# 02_POWER_LED.net
KiCad netlist of a schematic drawn in Altium Designer
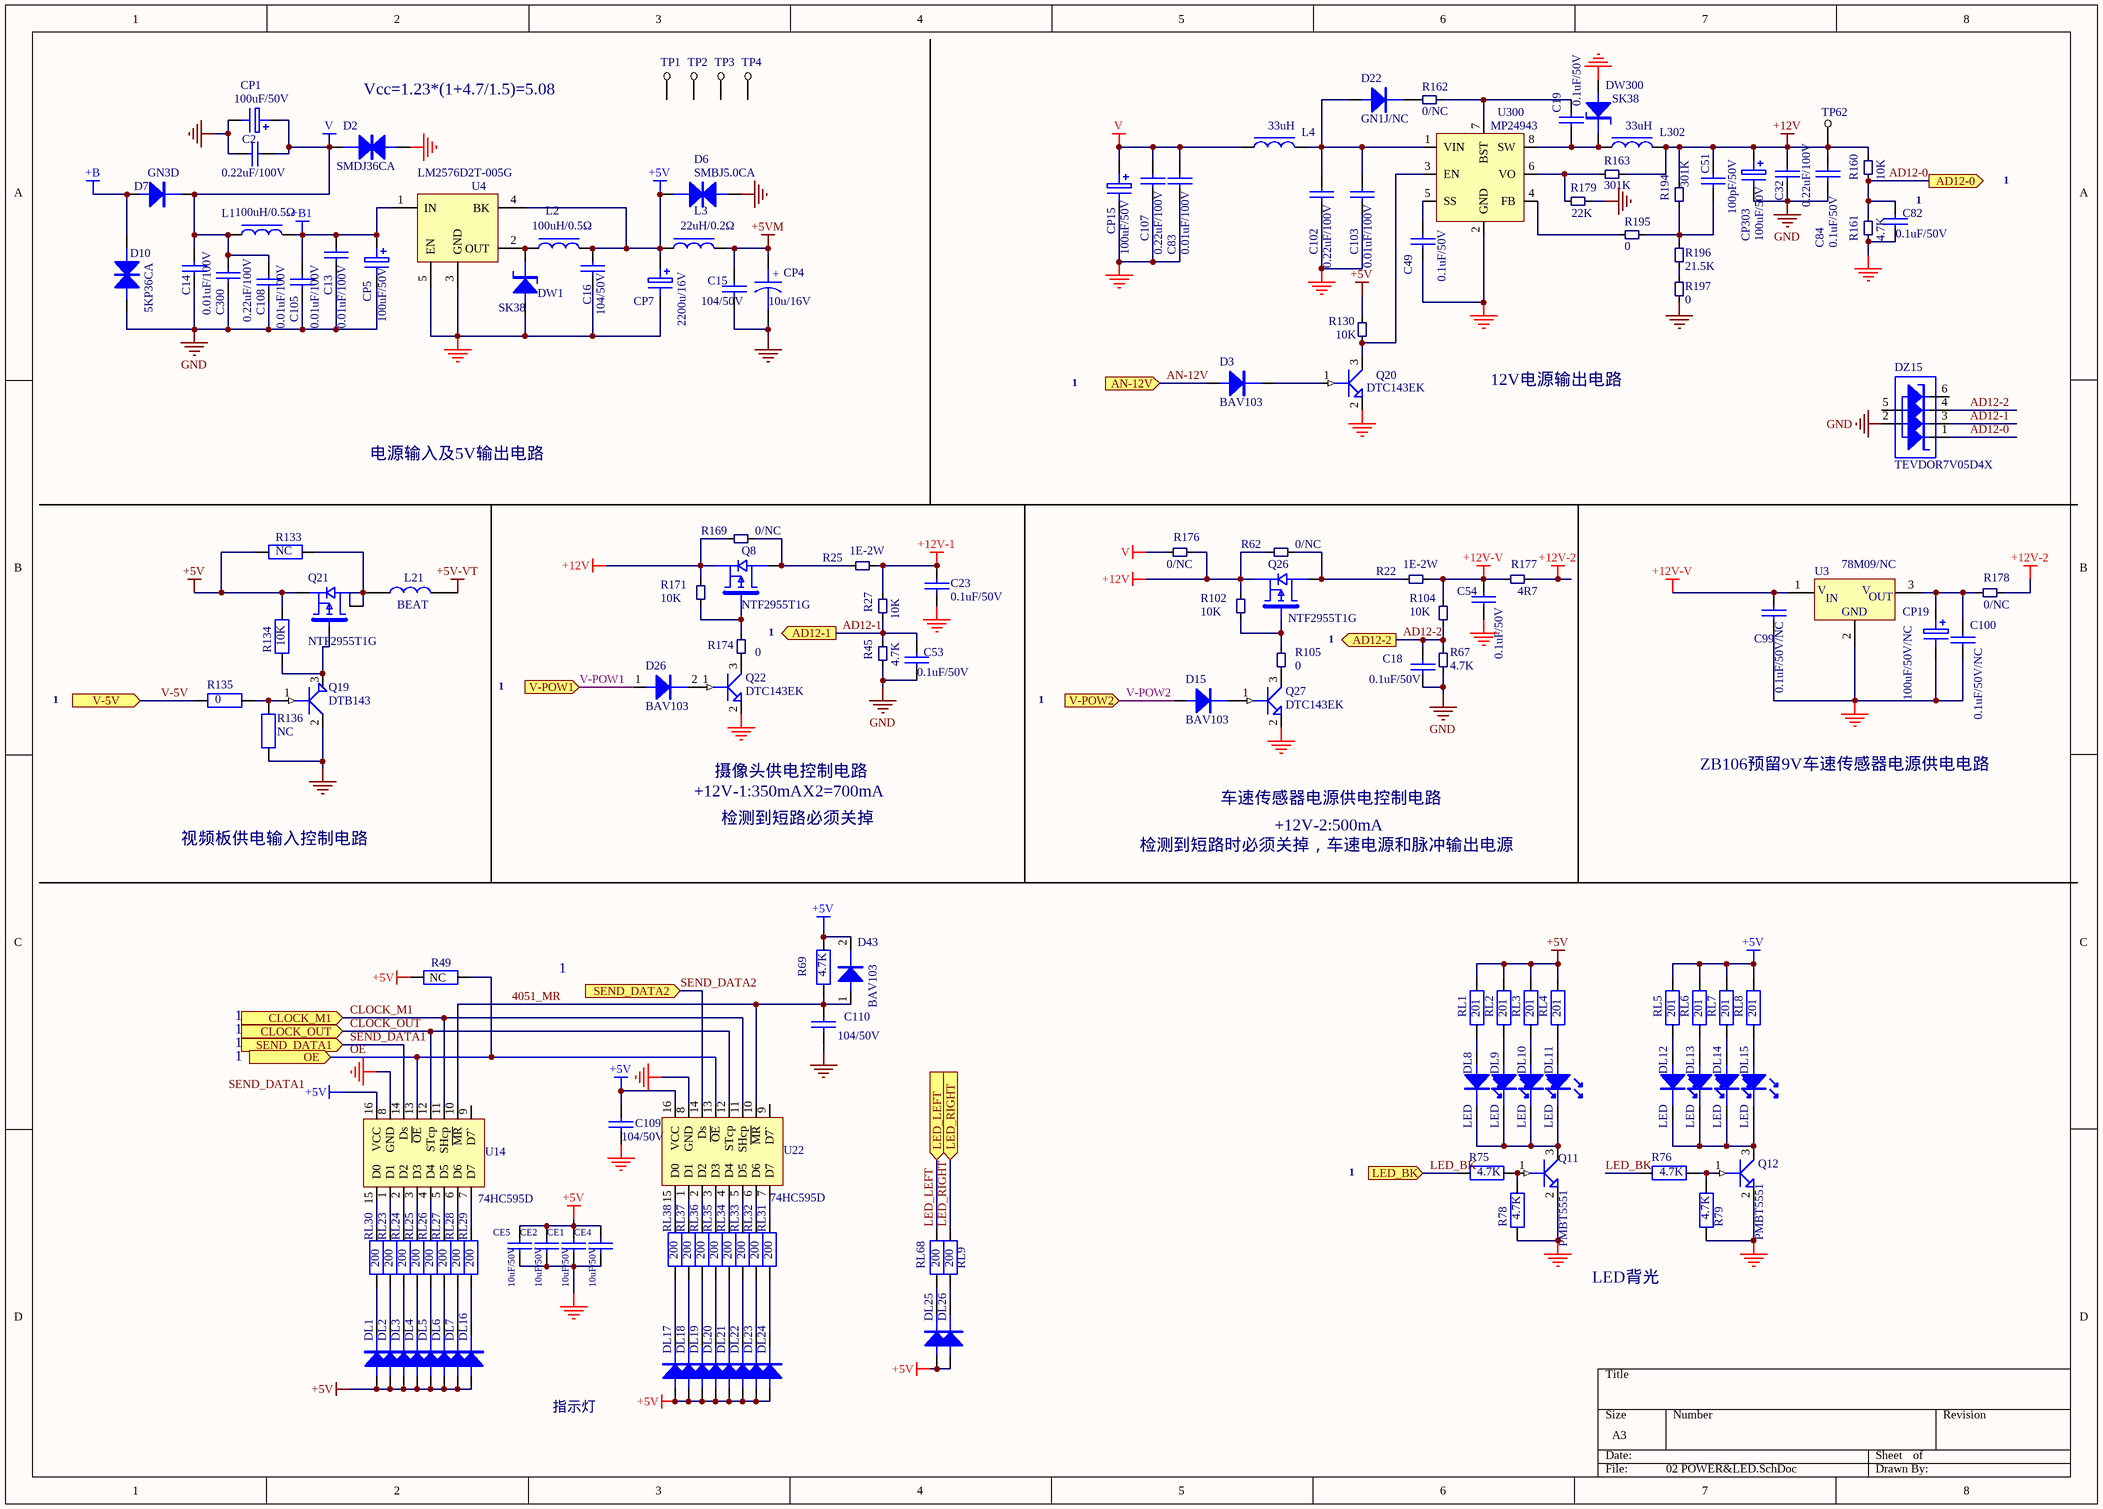
[diagram p0: 02 POWER&LED.SchDoc]

(export (version "E")
  (design (tool "Eeschema 10.0.6"))
  (components
    (comp (ref "C2")
      (value "0.22uF/100V")
      (footprint "CR1206")
      (description "Capacitor")
      (libsource (lib "*") (part "CAP"))
    )
    (comp (ref "C13")
      (value "0.01uF/100V")
      (footprint "CR0805")
      (description "Capacitor")
      (libsource (lib "*") (part "CAP"))
    )
    (comp (ref "C14")
      (value "0.01uF/100V")
      (footprint "CR0805")
      (description "Capacitor")
      (libsource (lib "*") (part "CAP"))
    )
    (comp (ref "C15")
      (value "104/50V")
      (footprint "CR0805")
      (description "Capacitor")
      (libsource (lib "*") (part "CAP"))
    )
    (comp (ref "C16")
      (value "104/50V")
      (footprint "CR0805")
      (description "Capacitor")
      (libsource (lib "*") (part "CAP"))
    )
    (comp (ref "C18")
      (value "0.1uF/50V")
      (footprint "CR0805")
      (description "Capacitor")
      (libsource (lib "*") (part "CAP"))
    )
    (comp (ref "C19")
      (value "0.1uF/50V")
      (footprint "CR0805")
      (description "Capacitor")
      (libsource (lib "*") (part "CAP"))
    )
    (comp (ref "C23")
      (value "0.1uF/50V")
      (footprint "CR0805")
      (description "Capacitor")
      (libsource (lib "*") (part "CAP"))
    )
    (comp (ref "C32")
      (value "0.22uF/100V")
      (footprint "CR1206")
      (description "Capacitor")
      (libsource (lib "*") (part "CAP"))
    )
    (comp (ref "C49")
      (value "0.1uF/50V")
      (footprint "CR0805")
      (description "Capacitor")
      (libsource (lib "*") (part "CAP"))
    )
    (comp (ref "C51")
      (value "100pF/50V")
      (footprint "CR0805")
      (description "Capacitor")
      (libsource (lib "*") (part "CAP"))
    )
    (comp (ref "C53")
      (value "0.1uF/50V")
      (footprint "CR0805")
      (description "Capacitor")
      (libsource (lib "*") (part "CAP"))
    )
    (comp (ref "C54")
      (value "0.1uF/50V")
      (footprint "CR0805")
      (description "Capacitor")
      (libsource (lib "*") (part "CAP"))
    )
    (comp (ref "C82")
      (value "0.1uF/50V")
      (footprint "CR0805")
      (description "Capacitor")
      (libsource (lib "*") (part "CAP"))
    )
    (comp (ref "C83")
      (value "0.01uF/100V")
      (footprint "CR0805")
      (description "Capacitor")
      (libsource (lib "*") (part "CAP"))
    )
    (comp (ref "C84")
      (value "0.1uF/50V")
      (footprint "CR0805")
      (description "Capacitor")
      (libsource (lib "*") (part "CAP"))
    )
    (comp (ref "C99")
      (value "0.1uF/50V/NC")
      (footprint "CR0805")
      (description "Capacitor")
      (libsource (lib "*") (part "CAP"))
    )
    (comp (ref "C100")
      (value "0.1uF/50V/NC")
      (footprint "CR0805")
      (description "Capacitor")
      (libsource (lib "*") (part "CAP"))
    )
    (comp (ref "C102")
      (value "0.22uF/100V")
      (footprint "CR1206")
      (description "Capacitor")
      (libsource (lib "*") (part "CAP"))
    )
    (comp (ref "C103")
      (value "0.01uF/100V")
      (footprint "CR0805")
      (description "Capacitor")
      (libsource (lib "*") (part "CAP"))
    )
    (comp (ref "C105")
      (value "0.01uF/100V")
      (footprint "CR0805")
      (description "Capacitor")
      (libsource (lib "*") (part "CAP"))
    )
    (comp (ref "C107")
      (value "0.22uF/100V")
      (footprint "CR1206")
      (description "Capacitor")
      (libsource (lib "*") (part "CAP"))
    )
    (comp (ref "C108")
      (value "0.01uF/100V")
      (footprint "CR0805")
      (description "Capacitor")
      (libsource (lib "*") (part "CAP"))
    )
    (comp (ref "C109")
      (value "104/50V")
      (footprint "CR0805")
      (description "Capacitor")
      (libsource (lib "*") (part "CAP"))
    )
    (comp (ref "C110")
      (value "104/50V")
      (footprint "CR0805")
      (description "Capacitor")
      (libsource (lib "*") (part "CAP"))
    )
    (comp (ref "C300")
      (value "0.22uF/100V")
      (footprint "CR1206")
      (description "Capacitor")
      (libsource (lib "*") (part "CAP"))
    )
    (comp (ref "CE1")
      (value "10uF/50V")
      (footprint "CR1206")
      (description "Capacitor")
      (libsource (lib "*") (part "CAP"))
    )
    (comp (ref "CE2")
      (value "10uF/50V")
      (footprint "CR1206")
      (description "Capacitor")
      (libsource (lib "*") (part "CAP"))
    )
    (comp (ref "CE4")
      (value "10uF/50V")
      (footprint "CR1206")
      (description "Capacitor")
      (libsource (lib "*") (part "CAP"))
    )
    (comp (ref "CE5")
      (value "10uF/50V")
      (footprint "CR1206")
      (description "Capacitor")
      (libsource (lib "*") (part "CAP"))
    )
    (comp (ref "CP1")
      (value "100uF/50V")
      (footprint "RB10")
      (description "电解电容")
      (libsource (lib "*") (part "ELECTRO1"))
    )
    (comp (ref "CP4")
      (value "10u/16V")
      (footprint "CE1206")
      (description "Capacitor")
      (libsource (lib "*") (part "CAPACITOR POL"))
    )
    (comp (ref "CP5")
      (value "100uF/50V")
      (footprint "RB5-1")
      (description "电解电容")
      (libsource (lib "*") (part "ELECTRO1"))
    )
    (comp (ref "CP7")
      (value "2200u/16V")
      (footprint "RB12.5")
      (description "电解电容")
      (libsource (lib "*") (part "ELECTRO1"))
    )
    (comp (ref "CP15")
      (value "100uF/50V")
      (footprint "RB5-1")
      (description "电解电容")
      (libsource (lib "*") (part "ELECTRO1"))
    )
    (comp (ref "CP19")
      (value "100uF/50V/NC")
      (footprint "RB5-1")
      (description "电解电容")
      (libsource (lib "*") (part "ELECTRO1"))
    )
    (comp (ref "CP303")
      (value "100uF/50V")
      (footprint "RB5-1")
      (description "电解电容")
      (libsource (lib "*") (part "ELECTRO1"))
    )
    (comp (ref "D2") (value "SMDJ36CA") (footprint "SMC-D") (libsource (lib "YDM-SQ-1SCH") (part "TVS")))
    (comp (ref "D3")
      (value "BAV103")
      (footprint "SOD-80C")
      (description "二极管")
      (libsource (lib "*") (part "DIODE"))
    )
    (comp (ref "D6") (value "SMBJ5.0CA") (footprint "SMB-D") (libsource (lib "YDM-SQ-1SCH") (part "TVS")))
    (comp (ref "D7")
      (value "GN3D")
      (footprint "SMC")
      (description "二极管")
      (libsource (lib "*") (part "DIODE"))
    )
    (comp (ref "D10") (value "5KP36CA") (footprint "D-17") (libsource (lib "*") (part "TVS")))
    (comp (ref "D15")
      (value "BAV103")
      (footprint "SOD-80C")
      (description "二极管")
      (libsource (lib "*") (part "DIODE"))
    )
    (comp (ref "D22")
      (value "GN1J/NC")
      (footprint "SMA")
      (description "二极管")
      (libsource (lib "*") (part "DIODE"))
    )
    (comp (ref "D26")
      (value "BAV103")
      (footprint "SOD-80C")
      (description "二极管")
      (libsource (lib "") (part "DIODE_1"))
    )
    (comp (ref "D43")
      (value "BAV103")
      (footprint "SOD-80C")
      (description "二极管")
      (libsource (lib "") (part "DIODE_1"))
    )
    (comp (ref "DL1")
      (value "~")
      (footprint "LED1210")
      (description "贴片二极管")
      (libsource (lib "*") (part "DOS"))
    )
    (comp (ref "DL2")
      (value "~")
      (footprint "LED1210")
      (description "贴片二极管")
      (libsource (lib "*") (part "DOS"))
    )
    (comp (ref "DL3")
      (value "~")
      (footprint "LED1210")
      (description "贴片二极管")
      (libsource (lib "*") (part "DOS"))
    )
    (comp (ref "DL4")
      (value "~")
      (footprint "LED1210")
      (description "贴片二极管")
      (libsource (lib "*") (part "DOS"))
    )
    (comp (ref "DL5")
      (value "~")
      (footprint "LED1210")
      (description "贴片二极管")
      (libsource (lib "*") (part "DOS"))
    )
    (comp (ref "DL6")
      (value "~")
      (footprint "LED1210")
      (description "贴片二极管")
      (libsource (lib "*") (part "DOS"))
    )
    (comp (ref "DL7")
      (value "~")
      (footprint "LED1210")
      (description "贴片二极管")
      (libsource (lib "*") (part "DOS"))
    )
    (comp (ref "DL8")
      (value "LED")
      (footprint "LED1210")
      (description "贴片LED")
      (libsource (lib "*") (part "LED"))
    )
    (comp (ref "DL9")
      (value "LED")
      (footprint "LED1210")
      (description "贴片LED")
      (libsource (lib "*") (part "LED"))
    )
    (comp (ref "DL10")
      (value "LED")
      (footprint "LED1210")
      (description "贴片LED")
      (libsource (lib "*") (part "LED"))
    )
    (comp (ref "DL11")
      (value "LED")
      (footprint "LED1210")
      (description "贴片LED")
      (libsource (lib "*") (part "LED"))
    )
    (comp (ref "DL12")
      (value "LED")
      (footprint "LED1210")
      (description "贴片LED")
      (libsource (lib "*") (part "LED"))
    )
    (comp (ref "DL13")
      (value "LED")
      (footprint "LED1210")
      (description "贴片LED")
      (libsource (lib "*") (part "LED"))
    )
    (comp (ref "DL14")
      (value "LED")
      (footprint "LED1210")
      (description "贴片LED")
      (libsource (lib "*") (part "LED"))
    )
    (comp (ref "DL15")
      (value "LED")
      (footprint "LED1210")
      (description "贴片LED")
      (libsource (lib "*") (part "LED"))
    )
    (comp (ref "DL16")
      (value "~")
      (footprint "LED1210")
      (description "贴片二极管")
      (libsource (lib "*") (part "DOS"))
    )
    (comp (ref "DL17")
      (value "~")
      (footprint "LED1210")
      (description "贴片二极管")
      (libsource (lib "*") (part "DOS"))
    )
    (comp (ref "DL18")
      (value "~")
      (footprint "LED1210")
      (description "贴片二极管")
      (libsource (lib "*") (part "DOS"))
    )
    (comp (ref "DL19")
      (value "~")
      (footprint "LED1210")
      (description "贴片二极管")
      (libsource (lib "*") (part "DOS"))
    )
    (comp (ref "DL20")
      (value "~")
      (footprint "LED1210")
      (description "贴片二极管")
      (libsource (lib "*") (part "DOS"))
    )
    (comp (ref "DL21")
      (value "~")
      (footprint "LED1210")
      (description "贴片二极管")
      (libsource (lib "*") (part "DOS"))
    )
    (comp (ref "DL22")
      (value "~")
      (footprint "LED1210")
      (description "贴片二极管")
      (libsource (lib "*") (part "DOS"))
    )
    (comp (ref "DL23")
      (value "~")
      (footprint "LED1210")
      (description "贴片二极管")
      (libsource (lib "*") (part "DOS"))
    )
    (comp (ref "DL24")
      (value "~")
      (footprint "LED1210")
      (description "贴片二极管")
      (libsource (lib "*") (part "DOS"))
    )
    (comp (ref "DL25")
      (value "~")
      (footprint "LED1210")
      (description "贴片二极管")
      (libsource (lib "*") (part "DOS"))
    )
    (comp (ref "DL26")
      (value "~")
      (footprint "LED1210")
      (description "贴片二极管")
      (libsource (lib "*") (part "DOS"))
    )
    (comp (ref "DW1")
      (value "SK38")
      (footprint "SMC")
      (description "稳压二极管")
      (libsource (lib "*") (part "DW"))
    )
    (comp (ref "DW300")
      (value "SK38")
      (footprint "SMC")
      (description "稳压二极管")
      (libsource (lib "*") (part "DW"))
    )
    (comp (ref "DZ15")
      (value "TEVDOR7V05D4X")
      (footprint "SOT-457")
      (description "二极管排")
      (libsource (lib "yibiaoschlib") (part "TEVDOR7V05D4X"))
    )
    (comp (ref "L1")
      (value "100uH/0.5Ω")
      (footprint "Ind-R13-7-100")
      (description "电感")
      (libsource (lib "*") (part "L"))
    )
    (comp (ref "L2")
      (value "100uH/0.5Ω")
      (footprint "Ind-R13-7-100")
      (description "电感")
      (libsource (lib "*") (part "L"))
    )
    (comp (ref "L3")
      (value "22uH/0.2Ω")
      (footprint "SS0603")
      (description "SS0603220ML")
      (libsource (lib "*") (part "L"))
    )
    (comp (ref "L4")
      (value "33uH")
      (footprint "Ind-R13-7-100")
      (description "电感")
      (libsource (lib "*") (part "L"))
    )
    (comp (ref "L21") (value "BEAT") (footprint "CR0805") (libsource (lib "YDM-SQ-1SCH") (part "BEAT")))
    (comp (ref "L302")
      (value "33uH")
      (footprint "Ind-R13-7-100")
      (description "电感")
      (libsource (lib "*") (part "L"))
    )
    (comp (ref "Q8")
      (value "NTF2955T1G")
      (footprint "SOT-223")
      (description "MOS")
      (libsource (lib "Ô­ÀíÍ¼¿â-1SCH") (part "MOS-P"))
    )
    (comp (ref "Q11")
      (value "PMBT5551")
      (footprint "SOT23")
      (description "PNP   三极管")
      (libsource (lib "Ô­ÀíÍ¼¿â-1SCH") (part "PMBT5551"))
    )
    (comp (ref "Q12")
      (value "PMBT5551")
      (footprint "SOT23")
      (description "PNP   三极管")
      (libsource (lib "Ô­ÀíÍ¼¿â-1SCH") (part "PMBT5551"))
    )
    (comp (ref "Q19") (value "DTB143") (footprint "SOT23") (libsource (lib "Ô­ÀíÍ¼¿â-1SCH") (part "BCX53")))
    (comp (ref "Q20")
      (value "DTC143EK")
      (footprint "SOT23")
      (description "NPN")
      (libsource (lib "Ô­ÀíÍ¼¿â-1SCH") (part "DTC143"))
    )
    (comp (ref "Q21")
      (value "NTF2955T1G")
      (footprint "SOT-223")
      (description "MOS")
      (libsource (lib "yibiaoschlib") (part "NTF2955T1G"))
    )
    (comp (ref "Q22")
      (value "DTC143EK")
      (footprint "SOT23")
      (description "NPN")
      (libsource (lib "Ô­ÀíÍ¼¿â-1SCH") (part "DTC143"))
    )
    (comp (ref "Q26")
      (value "NTF2955T1G")
      (footprint "SOT-223")
      (description "MOS")
      (libsource (lib "Ô­ÀíÍ¼¿â-1SCH") (part "MOS-P"))
    )
    (comp (ref "Q27")
      (value "DTC143EK")
      (footprint "SOT23")
      (description "NPN")
      (libsource (lib "Ô­ÀíÍ¼¿â-1SCH") (part "DTC143"))
    )
    (comp (ref "R22")
      (value "1E-2W")
      (footprint "R2512")
      (description "贴片电阻")
      (libsource (lib "YDM-SQ-1SCH") (part "Resister mini"))
    )
    (comp (ref "R25")
      (value "1E-2W")
      (footprint "R2512")
      (description "贴片电阻")
      (libsource (lib "YDM-SQ-1SCH") (part "Resister mini"))
    )
    (comp (ref "R27")
      (value "10K")
      (footprint "CR0805")
      (description "贴片电阻")
      (libsource (lib "YDM-SQ-1SCH") (part "Resister mini"))
    )
    (comp (ref "R45")
      (value "4.7K")
      (footprint "CR0805")
      (description "贴片电阻")
      (libsource (lib "YDM-SQ-1SCH") (part "Resister mini"))
    )
    (comp (ref "R49")
      (value "NC")
      (footprint "CR0805")
      (description "贴片电阻")
      (libsource (lib "*") (part "RES"))
    )
    (comp (ref "R62")
      (value "0/NC")
      (footprint "CR1206")
      (description "贴片电阻")
      (libsource (lib "YDM-SQ-1SCH") (part "Resister mini"))
    )
    (comp (ref "R67")
      (value "4.7K")
      (footprint "CR0805")
      (description "贴片电阻")
      (libsource (lib "YDM-SQ-1SCH") (part "Resister mini"))
    )
    (comp (ref "R69")
      (value "4.7K")
      (footprint "CR0805")
      (description "贴片电阻")
      (libsource (lib "*") (part "RES"))
    )
    (comp (ref "R75")
      (value "4.7K")
      (footprint "CR0805")
      (description "贴片电阻")
      (libsource (lib "YDM-SQ-1SCH") (part "RES"))
    )
    (comp (ref "R76")
      (value "4.7K")
      (footprint "CR0805")
      (description "贴片电阻")
      (libsource (lib "YDM-SQ-1SCH") (part "RES"))
    )
    (comp (ref "R78")
      (value "4.7K")
      (footprint "CR0805")
      (description "贴片电阻")
      (libsource (lib "YDM-SQ-1SCH") (part "RES"))
    )
    (comp (ref "R79")
      (value "4.7K")
      (footprint "CR0805")
      (description "贴片电阻")
      (libsource (lib "YDM-SQ-1SCH") (part "RES"))
    )
    (comp (ref "R102")
      (value "10K")
      (footprint "CR0805")
      (description "贴片电阻")
      (libsource (lib "YDM-SQ-1SCH") (part "Resister mini"))
    )
    (comp (ref "R104")
      (value "10K")
      (footprint "CR0805")
      (description "贴片电阻")
      (libsource (lib "YDM-SQ-1SCH") (part "Resister mini"))
    )
    (comp (ref "R105")
      (value "0")
      (footprint "CR0805")
      (description "贴片电阻")
      (libsource (lib "YDM-SQ-1SCH") (part "Resister mini"))
    )
    (comp (ref "R130")
      (value "10K")
      (footprint "CR0805")
      (description "贴片电阻")
      (libsource (lib "YDM-SQ-1SCH") (part "Resister mini"))
    )
    (comp (ref "R133")
      (value "NC")
      (footprint "CR1206")
      (description "贴片电阻")
      (libsource (lib "YDM-SQ-1SCH") (part "RES"))
    )
    (comp (ref "R134")
      (value "10K")
      (footprint "CR0805")
      (description "贴片电阻")
      (libsource (lib "YDM-SQ-1SCH") (part "RES"))
    )
    (comp (ref "R135")
      (value "0")
      (footprint "CR0805")
      (description "贴片电阻")
      (libsource (lib "YDM-SQ-1SCH") (part "RES"))
    )
    (comp (ref "R136")
      (value "NC")
      (footprint "CR0805")
      (description "贴片电阻")
      (libsource (lib "YDM-SQ-1SCH") (part "RES"))
    )
    (comp (ref "R160")
      (value "10K")
      (footprint "CR0805")
      (description "贴片电阻")
      (libsource (lib "YDM-SQ-1SCH") (part "Resister mini"))
    )
    (comp (ref "R161")
      (value "4.7K")
      (footprint "CR0805")
      (description "贴片电阻")
      (libsource (lib "YDM-SQ-1SCH") (part "Resister mini"))
    )
    (comp (ref "R162")
      (value "0/NC")
      (footprint "CR0805")
      (description "贴片电阻")
      (libsource (lib "YDM-SQ-1SCH") (part "Resister mini"))
    )
    (comp (ref "R163")
      (value "301K")
      (footprint "CR0805")
      (description "贴片电阻")
      (libsource (lib "YDM-SQ-1SCH") (part "Resister mini"))
    )
    (comp (ref "R169")
      (value "0/NC")
      (footprint "CR1206")
      (description "贴片电阻")
      (libsource (lib "YDM-SQ-1SCH") (part "Resister mini"))
    )
    (comp (ref "R171")
      (value "10K")
      (footprint "CR0805")
      (description "贴片电阻")
      (libsource (lib "YDM-SQ-1SCH") (part "Resister mini"))
    )
    (comp (ref "R174")
      (value "0")
      (footprint "CR0805")
      (description "贴片电阻")
      (libsource (lib "YDM-SQ-1SCH") (part "Resister mini"))
    )
    (comp (ref "R176")
      (value "0/NC")
      (footprint "CR1206")
      (description "贴片电阻")
      (libsource (lib "YDM-SQ-1SCH") (part "Resister mini"))
    )
    (comp (ref "R177")
      (value "4R7")
      (footprint "CR1206")
      (description "贴片电阻")
      (libsource (lib "YDM-SQ-1SCH") (part "Resister mini"))
    )
    (comp (ref "R178")
      (value "0/NC")
      (footprint "CR1206")
      (description "贴片电阻")
      (libsource (lib "YDM-SQ-1SCH") (part "Resister mini"))
    )
    (comp (ref "R179")
      (value "22K")
      (footprint "CR0805")
      (description "贴片电阻")
      (libsource (lib "YDM-SQ-1SCH") (part "Resister mini"))
    )
    (comp (ref "R194")
      (value "301K")
      (footprint "CR0805")
      (description "贴片电阻")
      (libsource (lib "YDM-SQ-1SCH") (part "Resister mini"))
    )
    (comp (ref "R195")
      (value "0")
      (footprint "CR0805")
      (description "贴片电阻")
      (libsource (lib "YDM-SQ-1SCH") (part "Resister mini"))
    )
    (comp (ref "R196")
      (value "21.5K")
      (footprint "CR0805")
      (description "贴片电阻")
      (libsource (lib "YDM-SQ-1SCH") (part "Resister mini"))
    )
    (comp (ref "R197")
      (value "0")
      (footprint "CR0805")
      (description "贴片电阻")
      (libsource (lib "YDM-SQ-1SCH") (part "Resister mini"))
    )
    (comp (ref "RL1")
      (value "201")
      (footprint "CR0805")
      (description "贴片电阻")
      (libsource (lib "*") (part "RES"))
    )
    (comp (ref "RL2")
      (value "201")
      (footprint "CR0805")
      (description "贴片电阻")
      (libsource (lib "*") (part "RES"))
    )
    (comp (ref "RL3")
      (value "201")
      (footprint "CR0805")
      (description "贴片电阻")
      (libsource (lib "*") (part "RES"))
    )
    (comp (ref "RL4")
      (value "201")
      (footprint "CR0805")
      (description "贴片电阻")
      (libsource (lib "*") (part "RES"))
    )
    (comp (ref "RL5")
      (value "201")
      (footprint "CR0805")
      (description "贴片电阻")
      (libsource (lib "*") (part "RES"))
    )
    (comp (ref "RL6")
      (value "201")
      (footprint "CR0805")
      (description "贴片电阻")
      (libsource (lib "*") (part "RES"))
    )
    (comp (ref "RL7")
      (value "201")
      (footprint "CR0805")
      (description "贴片电阻")
      (libsource (lib "*") (part "RES"))
    )
    (comp (ref "RL8")
      (value "201")
      (footprint "CR0805")
      (description "贴片电阻")
      (libsource (lib "*") (part "RES"))
    )
    (comp (ref "RL9")
      (value "200")
      (footprint "CR0805")
      (description "贴片电阻")
      (libsource (lib "*") (part "RES"))
    )
    (comp (ref "RL23")
      (value "200")
      (footprint "CR0805")
      (description "贴片电阻")
      (libsource (lib "*") (part "RES"))
    )
    (comp (ref "RL24")
      (value "200")
      (footprint "CR0805")
      (description "贴片电阻")
      (libsource (lib "*") (part "RES"))
    )
    (comp (ref "RL25")
      (value "200")
      (footprint "CR0805")
      (description "贴片电阻")
      (libsource (lib "*") (part "RES"))
    )
    (comp (ref "RL26")
      (value "200")
      (footprint "CR0805")
      (description "贴片电阻")
      (libsource (lib "*") (part "RES"))
    )
    (comp (ref "RL27")
      (value "200")
      (footprint "CR0805")
      (description "贴片电阻")
      (libsource (lib "*") (part "RES"))
    )
    (comp (ref "RL28")
      (value "200")
      (footprint "CR0805")
      (description "贴片电阻")
      (libsource (lib "*") (part "RES"))
    )
    (comp (ref "RL29")
      (value "200")
      (footprint "CR0805")
      (description "贴片电阻")
      (libsource (lib "*") (part "RES"))
    )
    (comp (ref "RL30")
      (value "200")
      (footprint "CR0805")
      (description "贴片电阻")
      (libsource (lib "*") (part "RES"))
    )
    (comp (ref "RL31")
      (value "200")
      (footprint "CR0805")
      (description "贴片电阻")
      (libsource (lib "*") (part "RES"))
    )
    (comp (ref "RL32")
      (value "200")
      (footprint "CR0805")
      (description "贴片电阻")
      (libsource (lib "*") (part "RES"))
    )
    (comp (ref "RL33")
      (value "200")
      (footprint "CR0805")
      (description "贴片电阻")
      (libsource (lib "*") (part "RES"))
    )
    (comp (ref "RL34")
      (value "200")
      (footprint "CR0805")
      (description "贴片电阻")
      (libsource (lib "*") (part "RES"))
    )
    (comp (ref "RL35")
      (value "200")
      (footprint "CR0805")
      (description "贴片电阻")
      (libsource (lib "*") (part "RES"))
    )
    (comp (ref "RL36")
      (value "200")
      (footprint "CR0805")
      (description "贴片电阻")
      (libsource (lib "*") (part "RES"))
    )
    (comp (ref "RL37")
      (value "200")
      (footprint "CR0805")
      (description "贴片电阻")
      (libsource (lib "*") (part "RES"))
    )
    (comp (ref "RL38")
      (value "200")
      (footprint "CR0805")
      (description "贴片电阻")
      (libsource (lib "*") (part "RES"))
    )
    (comp (ref "RL68")
      (value "200")
      (footprint "CR0805")
      (description "贴片电阻")
      (libsource (lib "*") (part "RES"))
    )
    (comp (ref "TP1") (value "TP") (footprint "MARK") (libsource (lib "YDM-SQ-1SCH") (part "TP")))
    (comp (ref "TP2") (value "TP") (footprint "MARK") (libsource (lib "YDM-SQ-1SCH") (part "TP")))
    (comp (ref "TP3") (value "TP") (footprint "MARK") (libsource (lib "YDM-SQ-1SCH") (part "TP")))
    (comp (ref "TP4") (value "TP") (footprint "MARK") (libsource (lib "YDM-SQ-1SCH") (part "TP")))
    (comp (ref "TP62") (value "~") (footprint "TP") (libsource (lib "YDM-SQ-1SCH") (part "TP")))
    (comp (ref "U3")
      (value "78M09/NC")
      (footprint "DPAK")
      (description "IC-三端稳压")
      (libsource (lib "HNS-SCH") (part "78M12"))
    )
    (comp (ref "U4")
      (value "LM2576D2T-005G")
      (footprint "SOT-263-5")
      (description "DC/DC")
      (libsource (lib "*") (part "LDO_1"))
    )
    (comp (ref "U14") (value "74HC595D") (footprint "SO-16") (libsource (lib "*") (part "74HC595D")))
    (comp (ref "U22") (value "74HC595D") (footprint "SO-16") (libsource (lib "*") (part "74HC595D")))
    (comp (ref "U300")
      (value "MP24943")
      (footprint "SOIC8E")
      (description "IC-CAN DRIVER")
      (libsource (lib "Ô­ÀíÍ¼¿â-1SCH") (part "MP24943"))
    )
  )
  (nets
    (net (code "1") (name "+5V") (class "Default")
      (node (ref "C109") (pin "2") (pinfunction "2_2") (pintype "passive"))
      (node (ref "C16") (pin "2") (pinfunction "2_2") (pintype "passive"))
      (node (ref "CE1") (pin "1") (pinfunction "1_1") (pintype "passive"))
      (node (ref "CE2") (pin "1") (pinfunction "1_1") (pintype "passive"))
      (node (ref "CE4") (pin "1") (pinfunction "1_1") (pintype "passive"))
      (node (ref "CE5") (pin "1") (pinfunction "1_1") (pintype "passive"))
      (node (ref "CP7") (pin "1") (pinfunction "1_1") (pintype "passive"))
      (node (ref "D43") (pin "2") (pinfunction "K_2") (pintype "passive"))
      (node (ref "D6") (pin "1") (pinfunction "1_1") (pintype "passive"))
      (node (ref "DL1") (pin "1") (pinfunction "A_1") (pintype "passive"))
      (node (ref "DL16") (pin "1") (pinfunction "A_1") (pintype "passive"))
      (node (ref "DL17") (pin "1") (pinfunction "A_1") (pintype "passive"))
      (node (ref "DL18") (pin "1") (pinfunction "A_1") (pintype "passive"))
      (node (ref "DL19") (pin "1") (pinfunction "A_1") (pintype "passive"))
      (node (ref "DL2") (pin "1") (pinfunction "A_1") (pintype "passive"))
      (node (ref "DL20") (pin "1") (pinfunction "A_1") (pintype "passive"))
      (node (ref "DL21") (pin "1") (pinfunction "A_1") (pintype "passive"))
      (node (ref "DL22") (pin "1") (pinfunction "A_1") (pintype "passive"))
      (node (ref "DL23") (pin "1") (pinfunction "A_1") (pintype "passive"))
      (node (ref "DL24") (pin "1") (pinfunction "A_1") (pintype "passive"))
      (node (ref "DL25") (pin "1") (pinfunction "A_1") (pintype "passive"))
      (node (ref "DL26") (pin "1") (pinfunction "A_1") (pintype "passive"))
      (node (ref "DL3") (pin "1") (pinfunction "A_1") (pintype "passive"))
      (node (ref "DL4") (pin "1") (pinfunction "A_1") (pintype "passive"))
      (node (ref "DL5") (pin "1") (pinfunction "A_1") (pintype "passive"))
      (node (ref "DL6") (pin "1") (pinfunction "A_1") (pintype "passive"))
      (node (ref "DL7") (pin "1") (pinfunction "A_1") (pintype "passive"))
      (node (ref "L2") (pin "2") (pinfunction "2_2") (pintype "passive"))
      (node (ref "L3") (pin "1") (pinfunction "1_1") (pintype "passive"))
      (node (ref "Q21") (pin "3") (pinfunction "S_3") (pintype "passive"))
      (node (ref "R130") (pin "1") (pinfunction "1_1") (pintype "passive"))
      (node (ref "R133") (pin "1") (pinfunction "1_1") (pintype "passive"))
      (node (ref "R134") (pin "1") (pinfunction "1_1") (pintype "passive"))
      (node (ref "R49") (pin "1") (pinfunction "1_1") (pintype "passive"))
      (node (ref "R69") (pin "2") (pinfunction "2_2") (pintype "passive"))
      (node (ref "RL1") (pin "1") (pinfunction "1_1") (pintype "passive"))
      (node (ref "RL2") (pin "1") (pinfunction "1_1") (pintype "passive"))
      (node (ref "RL3") (pin "1") (pinfunction "1_1") (pintype "passive"))
      (node (ref "RL4") (pin "1") (pinfunction "1_1") (pintype "passive"))
      (node (ref "RL5") (pin "1") (pinfunction "1_1") (pintype "passive"))
      (node (ref "RL6") (pin "1") (pinfunction "1_1") (pintype "passive"))
      (node (ref "RL7") (pin "1") (pinfunction "1_1") (pintype "passive"))
      (node (ref "RL8") (pin "1") (pinfunction "1_1") (pintype "passive"))
      (node (ref "U14") (pin "16") (pinfunction "VCC_16") (pintype "passive"))
      (node (ref "U22") (pin "16") (pinfunction "VCC_16") (pintype "passive"))
      (node (ref "U4") (pin "4") (pinfunction "BK_4") (pintype "passive"))
    )
    (net (code "2") (name "+5V-VT") (class "Default")
      (node (ref "L21") (pin "2") (pinfunction "2_2") (pintype "passive"))
    )
    (net (code "3") (name "+5VM") (class "Default")
      (node (ref "C15") (pin "1") (pinfunction "1_1") (pintype "passive"))
      (node (ref "CP4") (pin "1") (pinfunction "1_1") (pintype "passive"))
      (node (ref "L3") (pin "2") (pinfunction "2_2") (pintype "passive"))
    )
    (net (code "4") (name "+12V") (class "Default")
      (node (ref "C32") (pin "2") (pinfunction "2_2") (pintype "passive"))
      (node (ref "C51") (pin "2") (pinfunction "2_2") (pintype "passive"))
      (node (ref "C84") (pin "2") (pinfunction "2_2") (pintype "passive"))
      (node (ref "CP303") (pin "1") (pinfunction "1_1") (pintype "passive"))
      (node (ref "L302") (pin "2") (pinfunction "2_2") (pintype "passive"))
      (node (ref "Q26") (pin "3") (pintype "passive"))
      (node (ref "Q8") (pin "3") (pintype "passive"))
      (node (ref "R102") (pin "2") (pinfunction "2_2") (pintype "passive"))
      (node (ref "R160") (pin "2") (pinfunction "2_2") (pintype "passive"))
      (node (ref "R163") (pin "2") (pinfunction "2_2") (pintype "passive"))
      (node (ref "R169") (pin "1") (pinfunction "1_1") (pintype "passive"))
      (node (ref "R171") (pin "2") (pinfunction "2_2") (pintype "passive"))
      (node (ref "R176") (pin "2") (pinfunction "2_2") (pintype "passive"))
      (node (ref "R194") (pin "1") (pinfunction "1_1") (pintype "passive"))
      (node (ref "R62") (pin "1") (pinfunction "1_1") (pintype "passive"))
      (node (ref "TP62") (pin "1") (pinfunction "1_1") (pintype "passive"))
    )
    (net (code "5") (name "+12V-1") (class "Default")
      (node (ref "C23") (pin "1") (pinfunction "1_1") (pintype "passive"))
      (node (ref "R25") (pin "2") (pinfunction "2_2") (pintype "passive"))
      (node (ref "R27") (pin "2") (pinfunction "2_2") (pintype "passive"))
    )
    (net (code "6") (name "+12V-2") (class "Default")
      (node (ref "R177") (pin "2") (pinfunction "2_2") (pintype "passive"))
      (node (ref "R178") (pin "2") (pinfunction "2_2") (pintype "passive"))
    )
    (net (code "7") (name "+12V-V") (class "Default")
      (node (ref "C54") (pin "1") (pinfunction "1_1") (pintype "passive"))
      (node (ref "C99") (pin "2") (pinfunction "2_2") (pintype "passive"))
      (node (ref "R104") (pin "2") (pinfunction "2_2") (pintype "passive"))
      (node (ref "R177") (pin "1") (pinfunction "1_1") (pintype "passive"))
      (node (ref "R22") (pin "2") (pinfunction "2_2") (pintype "passive"))
      (node (ref "U3") (pin "1") (pinfunction "VIN_1") (pintype "passive"))
    )
    (net (code "8") (name "+B") (class "Default")
      (node (ref "D10") (pin "1") (pinfunction "1_1") (pintype "passive"))
      (node (ref "D7") (pin "1") (pinfunction "A_1") (pintype "passive"))
    )
    (net (code "9") (name "+B1") (class "Default")
      (node (ref "C105") (pin "2") (pinfunction "2_2") (pintype "passive"))
      (node (ref "C13") (pin "2") (pinfunction "2_2") (pintype "passive"))
      (node (ref "CP5") (pin "1") (pinfunction "1_1") (pintype "passive"))
      (node (ref "L1") (pin "2") (pinfunction "2_2") (pintype "passive"))
      (node (ref "U4") (pin "1") (pinfunction "IN_1") (pintype "passive"))
    )
    (net (code "10") (name "/4051_MR") (class "Default")
      (node (ref "C110") (pin "1") (pinfunction "1_1") (pintype "passive"))
      (node (ref "D43") (pin "1") (pinfunction "A_1") (pintype "passive"))
      (node (ref "R69") (pin "1") (pinfunction "1_1") (pintype "passive"))
      (node (ref "U14") (pin "10") (pinfunction "~{MR}_10") (pintype "passive"))
      (node (ref "U22") (pin "10") (pinfunction "~{MR}_10") (pintype "passive"))
    )
    (net (code "11") (name "/AD12-0") (class "Default")
      (node (ref "C82") (pin "2") (pinfunction "2_2") (pintype "passive"))
      (node (ref "DZ15") (pin "1") (pintype "passive"))
      (node (ref "R160") (pin "1") (pinfunction "1_1") (pintype "passive"))
      (node (ref "R161") (pin "2") (pinfunction "2_2") (pintype "passive"))
    )
    (net (code "12") (name "/AD12-1") (class "Default")
      (node (ref "C53") (pin "2") (pinfunction "2_2") (pintype "passive"))
      (node (ref "DZ15") (pin "3") (pintype "passive"))
      (node (ref "R27") (pin "1") (pinfunction "1_1") (pintype "passive"))
      (node (ref "R45") (pin "2") (pinfunction "2_2") (pintype "passive"))
    )
    (net (code "13") (name "/AD12-2") (class "Default")
      (node (ref "C18") (pin "2") (pinfunction "2_2") (pintype "passive"))
      (node (ref "DZ15") (pin "4") (pintype "passive"))
      (node (ref "R104") (pin "1") (pinfunction "1_1") (pintype "passive"))
      (node (ref "R67") (pin "2") (pinfunction "2_2") (pintype "passive"))
    )
    (net (code "14") (name "/AN-12V") (class "Default")
      (node (ref "D3") (pin "1") (pinfunction "A_1") (pintype "passive"))
    )
    (net (code "15") (name "/CLOCK_M1") (class "Default")
      (node (ref "U14") (pin "11") (pinfunction "SHcp_11") (pintype "passive"))
      (node (ref "U22") (pin "11") (pinfunction "SHcp_11") (pintype "passive"))
    )
    (net (code "16") (name "/CLOCK_OUT") (class "Default")
      (node (ref "U14") (pin "12") (pinfunction "STcp_12") (pintype "passive"))
      (node (ref "U22") (pin "12") (pinfunction "STcp_12") (pintype "passive"))
    )
    (net (code "17") (name "/LED_BK") (class "Default")
      (node (ref "R75") (pin "1") (pinfunction "1_1") (pintype "passive"))
      (node (ref "R76") (pin "1") (pinfunction "1_1") (pintype "passive"))
    )
    (net (code "18") (name "/LED_LEFT") (class "Default")
      (node (ref "RL68") (pin "1") (pinfunction "1_1") (pintype "passive"))
    )
    (net (code "19") (name "/LED_RIGHT") (class "Default")
      (node (ref "RL9") (pin "1") (pinfunction "1_1") (pintype "passive"))
    )
    (net (code "20") (name "/OE") (class "Default")
      (node (ref "R49") (pin "2") (pinfunction "2_2") (pintype "passive"))
      (node (ref "U14") (pin "13") (pinfunction "~{OE}_13") (pintype "passive"))
      (node (ref "U22") (pin "13") (pinfunction "~{OE}_13") (pintype "passive"))
    )
    (net (code "21") (name "/SEND_DATA1") (class "Default")
      (node (ref "U14") (pin "14") (pinfunction "Ds_14") (pintype "passive"))
    )
    (net (code "22") (name "/SEND_DATA2") (class "Default")
      (node (ref "U22") (pin "14") (pinfunction "Ds_14") (pintype "passive"))
    )
    (net (code "23") (name "/V-5V") (class "Default")
      (node (ref "R135") (pin "1") (pinfunction "1_1") (pintype "passive"))
    )
    (net (code "24") (name "/V-POW1") (class "Default")
      (node (ref "D26") (pin "1") (pinfunction "A_1") (pintype "passive"))
    )
    (net (code "25") (name "/V-POW2") (class "Default")
      (node (ref "D15") (pin "1") (pinfunction "A_1") (pintype "passive"))
    )
    (net (code "26") (name "GND") (class "Default")
      (node (ref "C100") (pin "2") (pinfunction "2_2") (pintype "passive"))
      (node (ref "C102") (pin "1") (pinfunction "1_1") (pintype "passive"))
      (node (ref "C103") (pin "1") (pinfunction "1_1") (pintype "passive"))
      (node (ref "C105") (pin "1") (pinfunction "1_1") (pintype "passive"))
      (node (ref "C107") (pin "1") (pinfunction "1_1") (pintype "passive"))
      (node (ref "C108") (pin "1") (pinfunction "1_1") (pintype "passive"))
      (node (ref "C109") (pin "1") (pinfunction "1_1") (pintype "passive"))
      (node (ref "C110") (pin "2") (pinfunction "2_2") (pintype "passive"))
      (node (ref "C13") (pin "1") (pinfunction "1_1") (pintype "passive"))
      (node (ref "C14") (pin "1") (pinfunction "1_1") (pintype "passive"))
      (node (ref "C15") (pin "2") (pinfunction "2_2") (pintype "passive"))
      (node (ref "C16") (pin "1") (pinfunction "1_1") (pintype "passive"))
      (node (ref "C18") (pin "1") (pinfunction "1_1") (pintype "passive"))
      (node (ref "C2") (pin "1") (pinfunction "1_1") (pintype "passive"))
      (node (ref "C23") (pin "2") (pinfunction "2_2") (pintype "passive"))
      (node (ref "C300") (pin "1") (pinfunction "1_1") (pintype "passive"))
      (node (ref "C32") (pin "1") (pinfunction "1_1") (pintype "passive"))
      (node (ref "C49") (pin "1") (pinfunction "1_1") (pintype "passive"))
      (node (ref "C53") (pin "1") (pinfunction "1_1") (pintype "passive"))
      (node (ref "C54") (pin "2") (pinfunction "2_2") (pintype "passive"))
      (node (ref "C82") (pin "1") (pinfunction "1_1") (pintype "passive"))
      (node (ref "C83") (pin "1") (pinfunction "1_1") (pintype "passive"))
      (node (ref "C84") (pin "1") (pinfunction "1_1") (pintype "passive"))
      (node (ref "C99") (pin "1") (pinfunction "1_1") (pintype "passive"))
      (node (ref "CE1") (pin "2") (pinfunction "2_2") (pintype "passive"))
      (node (ref "CE2") (pin "2") (pinfunction "2_2") (pintype "passive"))
      (node (ref "CE4") (pin "2") (pinfunction "2_2") (pintype "passive"))
      (node (ref "CE5") (pin "2") (pinfunction "2_2") (pintype "passive"))
      (node (ref "CP1") (pin "2") (pinfunction "2_2") (pintype "passive"))
      (node (ref "CP15") (pin "2") (pinfunction "2_2") (pintype "passive"))
      (node (ref "CP19") (pin "2") (pinfunction "2_2") (pintype "passive"))
      (node (ref "CP303") (pin "2") (pinfunction "2_2") (pintype "passive"))
      (node (ref "CP4") (pin "2") (pinfunction "2_2") (pintype "passive"))
      (node (ref "CP5") (pin "2") (pinfunction "2_2") (pintype "passive"))
      (node (ref "CP7") (pin "2") (pinfunction "2_2") (pintype "passive"))
      (node (ref "D10") (pin "2") (pinfunction "2_2") (pintype "passive"))
      (node (ref "D2") (pin "2") (pinfunction "2_2") (pintype "passive"))
      (node (ref "D6") (pin "2") (pinfunction "2_2") (pintype "passive"))
      (node (ref "DW1") (pin "1") (pinfunction "A_1") (pintype "passive"))
      (node (ref "DW300") (pin "1") (pinfunction "A_1") (pintype "passive"))
      (node (ref "DZ15") (pin "2") (pintype "passive"))
      (node (ref "Q11") (pin "2") (pinfunction "E_2") (pintype "passive"))
      (node (ref "Q12") (pin "2") (pinfunction "E_2") (pintype "passive"))
      (node (ref "Q19") (pin "2") (pinfunction "c_2") (pintype "passive"))
      (node (ref "Q20") (pin "2") (pinfunction "gnd_2") (pintype "passive"))
      (node (ref "Q22") (pin "2") (pinfunction "gnd_2") (pintype "passive"))
      (node (ref "Q27") (pin "2") (pinfunction "gnd_2") (pintype "passive"))
      (node (ref "R136") (pin "1") (pinfunction "1_1") (pintype "passive"))
      (node (ref "R161") (pin "1") (pinfunction "1_1") (pintype "passive"))
      (node (ref "R179") (pin "1") (pinfunction "1_1") (pintype "passive"))
      (node (ref "R197") (pin "2") (pinfunction "2_2") (pintype "passive"))
      (node (ref "R45") (pin "1") (pinfunction "1_1") (pintype "passive"))
      (node (ref "R67") (pin "1") (pinfunction "1_1") (pintype "passive"))
      (node (ref "R78") (pin "2") (pinfunction "2_2") (pintype "passive"))
      (node (ref "R79") (pin "2") (pinfunction "2_2") (pintype "passive"))
      (node (ref "U14") (pin "8") (pinfunction "GND_8") (pintype "passive"))
      (node (ref "U22") (pin "8") (pinfunction "GND_8") (pintype "passive"))
      (node (ref "U3") (pin "2") (pinfunction "GND_2") (pintype "passive"))
      (node (ref "U300") (pin "2") (pinfunction "GND_2") (pintype "passive"))
      (node (ref "U4") (pin "3") (pinfunction "GND_3") (pintype "passive"))
      (node (ref "U4") (pin "5") (pinfunction "EN_5") (pintype "passive"))
    )
    (net (code "27") (name "Net-(C51-Pad1)") (class "Default")
      (node (ref "C51") (pin "1") (pinfunction "1_1") (pintype "passive"))
      (node (ref "R194") (pin "2") (pinfunction "2_2") (pintype "passive"))
      (node (ref "R195") (pin "1") (pinfunction "1_1") (pintype "passive"))
      (node (ref "R196") (pin "1") (pinfunction "1_1") (pintype "passive"))
    )
    (net (code "28") (name "Net-(D3-K)") (class "Default")
      (node (ref "D3") (pin "2") (pinfunction "K_2") (pintype "passive"))
      (node (ref "Q20") (pin "1") (pinfunction "in_1") (pintype "input"))
    )
    (net (code "29") (name "Net-(D15-K)") (class "Default")
      (node (ref "D15") (pin "2") (pinfunction "K_2") (pintype "passive"))
      (node (ref "Q27") (pin "1") (pinfunction "in_1") (pintype "input"))
    )
    (net (code "30") (name "Net-(D22-A)") (class "Default")
      (node (ref "C102") (pin "2") (pinfunction "2_2") (pintype "passive"))
      (node (ref "C103") (pin "2") (pinfunction "2_2") (pintype "passive"))
      (node (ref "D22") (pin "1") (pinfunction "A_1") (pintype "passive"))
      (node (ref "L4") (pin "2") (pinfunction "2_2") (pintype "passive"))
      (node (ref "U300") (pin "1") (pinfunction "VIN_1") (pintype "passive"))
    )
    (net (code "31") (name "Net-(D22-K)") (class "Default")
      (node (ref "D22") (pin "2") (pinfunction "K_2") (pintype "passive"))
      (node (ref "R162") (pin "2") (pinfunction "2_2") (pintype "passive"))
    )
    (net (code "32") (name "Net-(D26-K)") (class "Default")
      (node (ref "D26") (pin "2") (pinfunction "K_2") (pintype "passive"))
      (node (ref "Q22") (pin "1") (pinfunction "in_1") (pintype "input"))
    )
    (net (code "33") (name "Net-(DL1-K)") (class "Default")
      (node (ref "DL1") (pin "2") (pinfunction "K_2") (pintype "passive"))
      (node (ref "RL30") (pin "2") (pinfunction "2_2") (pintype "passive"))
    )
    (net (code "34") (name "Net-(DL2-K)") (class "Default")
      (node (ref "DL2") (pin "2") (pinfunction "K_2") (pintype "passive"))
      (node (ref "RL23") (pin "2") (pinfunction "2_2") (pintype "passive"))
    )
    (net (code "35") (name "Net-(DL3-K)") (class "Default")
      (node (ref "DL3") (pin "2") (pinfunction "K_2") (pintype "passive"))
      (node (ref "RL24") (pin "2") (pinfunction "2_2") (pintype "passive"))
    )
    (net (code "36") (name "Net-(DL4-K)") (class "Default")
      (node (ref "DL4") (pin "2") (pinfunction "K_2") (pintype "passive"))
      (node (ref "RL25") (pin "2") (pinfunction "2_2") (pintype "passive"))
    )
    (net (code "37") (name "Net-(DL5-K)") (class "Default")
      (node (ref "DL5") (pin "2") (pinfunction "K_2") (pintype "passive"))
      (node (ref "RL26") (pin "2") (pinfunction "2_2") (pintype "passive"))
    )
    (net (code "38") (name "Net-(DL6-K)") (class "Default")
      (node (ref "DL6") (pin "2") (pinfunction "K_2") (pintype "passive"))
      (node (ref "RL27") (pin "2") (pinfunction "2_2") (pintype "passive"))
    )
    (net (code "39") (name "Net-(DL7-K)") (class "Default")
      (node (ref "DL7") (pin "2") (pinfunction "K_2") (pintype "passive"))
      (node (ref "RL28") (pin "2") (pinfunction "2_2") (pintype "passive"))
    )
    (net (code "40") (name "Net-(DL8-Pad1)") (class "Default")
      (node (ref "DL8") (pin "1") (pinfunction "1_1") (pintype "passive"))
      (node (ref "RL1") (pin "2") (pinfunction "2_2") (pintype "passive"))
    )
    (net (code "41") (name "Net-(DL9-Pad1)") (class "Default")
      (node (ref "DL9") (pin "1") (pinfunction "1_1") (pintype "passive"))
      (node (ref "RL2") (pin "2") (pinfunction "2_2") (pintype "passive"))
    )
    (net (code "42") (name "Net-(DL10-Pad1)") (class "Default")
      (node (ref "DL10") (pin "1") (pinfunction "1_1") (pintype "passive"))
      (node (ref "RL3") (pin "2") (pinfunction "2_2") (pintype "passive"))
    )
    (net (code "43") (name "Net-(DL11-Pad1)") (class "Default")
      (node (ref "DL11") (pin "1") (pinfunction "1_1") (pintype "passive"))
      (node (ref "RL4") (pin "2") (pinfunction "2_2") (pintype "passive"))
    )
    (net (code "44") (name "Net-(DL12-Pad1)") (class "Default")
      (node (ref "DL12") (pin "1") (pinfunction "1_1") (pintype "passive"))
      (node (ref "RL5") (pin "2") (pinfunction "2_2") (pintype "passive"))
    )
    (net (code "45") (name "Net-(DL13-Pad1)") (class "Default")
      (node (ref "DL13") (pin "1") (pinfunction "1_1") (pintype "passive"))
      (node (ref "RL6") (pin "2") (pinfunction "2_2") (pintype "passive"))
    )
    (net (code "46") (name "Net-(DL14-Pad1)") (class "Default")
      (node (ref "DL14") (pin "1") (pinfunction "1_1") (pintype "passive"))
      (node (ref "RL7") (pin "2") (pinfunction "2_2") (pintype "passive"))
    )
    (net (code "47") (name "Net-(DL15-Pad1)") (class "Default")
      (node (ref "DL15") (pin "1") (pinfunction "1_1") (pintype "passive"))
      (node (ref "RL8") (pin "2") (pinfunction "2_2") (pintype "passive"))
    )
    (net (code "48") (name "Net-(DL16-K)") (class "Default")
      (node (ref "DL16") (pin "2") (pinfunction "K_2") (pintype "passive"))
      (node (ref "RL29") (pin "2") (pinfunction "2_2") (pintype "passive"))
    )
    (net (code "49") (name "Net-(DL17-K)") (class "Default")
      (node (ref "DL17") (pin "2") (pinfunction "K_2") (pintype "passive"))
      (node (ref "RL38") (pin "2") (pinfunction "2_2") (pintype "passive"))
    )
    (net (code "50") (name "Net-(DL18-K)") (class "Default")
      (node (ref "DL18") (pin "2") (pinfunction "K_2") (pintype "passive"))
      (node (ref "RL37") (pin "2") (pinfunction "2_2") (pintype "passive"))
    )
    (net (code "51") (name "Net-(DL19-K)") (class "Default")
      (node (ref "DL19") (pin "2") (pinfunction "K_2") (pintype "passive"))
      (node (ref "RL36") (pin "2") (pinfunction "2_2") (pintype "passive"))
    )
    (net (code "52") (name "Net-(DL20-K)") (class "Default")
      (node (ref "DL20") (pin "2") (pinfunction "K_2") (pintype "passive"))
      (node (ref "RL35") (pin "2") (pinfunction "2_2") (pintype "passive"))
    )
    (net (code "53") (name "Net-(DL21-K)") (class "Default")
      (node (ref "DL21") (pin "2") (pinfunction "K_2") (pintype "passive"))
      (node (ref "RL34") (pin "2") (pinfunction "2_2") (pintype "passive"))
    )
    (net (code "54") (name "Net-(DL22-K)") (class "Default")
      (node (ref "DL22") (pin "2") (pinfunction "K_2") (pintype "passive"))
      (node (ref "RL33") (pin "2") (pinfunction "2_2") (pintype "passive"))
    )
    (net (code "55") (name "Net-(DL23-K)") (class "Default")
      (node (ref "DL23") (pin "2") (pinfunction "K_2") (pintype "passive"))
      (node (ref "RL32") (pin "2") (pinfunction "2_2") (pintype "passive"))
    )
    (net (code "56") (name "Net-(DL24-K)") (class "Default")
      (node (ref "DL24") (pin "2") (pinfunction "K_2") (pintype "passive"))
      (node (ref "RL31") (pin "2") (pinfunction "2_2") (pintype "passive"))
    )
    (net (code "57") (name "Net-(DL25-K)") (class "Default")
      (node (ref "DL25") (pin "2") (pinfunction "K_2") (pintype "passive"))
      (node (ref "RL68") (pin "2") (pinfunction "2_2") (pintype "passive"))
    )
    (net (code "58") (name "Net-(DL26-K)") (class "Default")
      (node (ref "DL26") (pin "2") (pinfunction "K_2") (pintype "passive"))
      (node (ref "RL9") (pin "2") (pinfunction "2_2") (pintype "passive"))
    )
    (net (code "59") (name "Net-(DW1-K)") (class "Default")
      (node (ref "DW1") (pin "2") (pinfunction "K_2") (pintype "passive"))
      (node (ref "L2") (pin "1") (pinfunction "1_1") (pintype "passive"))
      (node (ref "U4") (pin "2") (pinfunction "OUT_2") (pintype "passive"))
    )
    (net (code "60") (name "Net-(DW300-K)") (class "Default")
      (node (ref "C19") (pin "1") (pinfunction "1_1") (pintype "passive"))
      (node (ref "DW300") (pin "2") (pinfunction "K_2") (pintype "passive"))
      (node (ref "L302") (pin "1") (pinfunction "1_1") (pintype "passive"))
      (node (ref "U300") (pin "8") (pinfunction "SW_8") (pintype "passive"))
    )
    (net (code "61") (name "Net-(L21-Pad1)") (class "Default")
      (node (ref "L21") (pin "1") (pinfunction "1_1") (pintype "passive"))
      (node (ref "Q21") (pin "2") (pinfunction "D_2") (pintype "passive"))
      (node (ref "Q21") (pin "4") (pinfunction "D_4") (pintype "passive"))
      (node (ref "R133") (pin "2") (pinfunction "2_2") (pintype "passive"))
    )
    (net (code "62") (name "Net-(Q8-Pad1)") (class "Default")
      (node (ref "Q8") (pin "1") (pintype "passive"))
      (node (ref "R171") (pin "1") (pinfunction "1_1") (pintype "passive"))
      (node (ref "R174") (pin "1") (pinfunction "1_1") (pintype "passive"))
    )
    (net (code "63") (name "Net-(Q8-Pad2)") (class "Default")
      (node (ref "Q8") (pin "2") (pintype "passive"))
      (node (ref "R169") (pin "2") (pinfunction "2_2") (pintype "passive"))
      (node (ref "R25") (pin "1") (pinfunction "1_1") (pintype "passive"))
    )
    (net (code "64") (name "Net-(Q11-B)") (class "Default")
      (node (ref "Q11") (pin "1") (pinfunction "B_1") (pintype "input"))
      (node (ref "R75") (pin "2") (pinfunction "2_2") (pintype "passive"))
      (node (ref "R78") (pin "1") (pinfunction "1_1") (pintype "passive"))
    )
    (net (code "65") (name "Net-(Q11-C)") (class "Default")
      (node (ref "DL10") (pin "2") (pinfunction "2_2") (pintype "passive"))
      (node (ref "DL11") (pin "2") (pinfunction "2_2") (pintype "passive"))
      (node (ref "DL8") (pin "2") (pinfunction "2_2") (pintype "passive"))
      (node (ref "DL9") (pin "2") (pinfunction "2_2") (pintype "passive"))
      (node (ref "Q11") (pin "3") (pinfunction "C_3") (pintype "passive"))
    )
    (net (code "66") (name "Net-(Q12-B)") (class "Default")
      (node (ref "Q12") (pin "1") (pinfunction "B_1") (pintype "input"))
      (node (ref "R76") (pin "2") (pinfunction "2_2") (pintype "passive"))
      (node (ref "R79") (pin "1") (pinfunction "1_1") (pintype "passive"))
    )
    (net (code "67") (name "Net-(Q12-C)") (class "Default")
      (node (ref "DL12") (pin "2") (pinfunction "2_2") (pintype "passive"))
      (node (ref "DL13") (pin "2") (pinfunction "2_2") (pintype "passive"))
      (node (ref "DL14") (pin "2") (pinfunction "2_2") (pintype "passive"))
      (node (ref "DL15") (pin "2") (pinfunction "2_2") (pintype "passive"))
      (node (ref "Q12") (pin "3") (pinfunction "C_3") (pintype "passive"))
    )
    (net (code "68") (name "Net-(Q19-b)") (class "Default")
      (node (ref "Q19") (pin "1") (pinfunction "b_1") (pintype "input"))
      (node (ref "R135") (pin "2") (pinfunction "2_2") (pintype "passive"))
      (node (ref "R136") (pin "2") (pinfunction "2_2") (pintype "passive"))
    )
    (net (code "69") (name "Net-(Q19-e)") (class "Default")
      (node (ref "Q19") (pin "3") (pinfunction "e_3") (pintype "passive"))
      (node (ref "Q21") (pin "1") (pinfunction "G_1") (pintype "passive"))
      (node (ref "R134") (pin "2") (pinfunction "2_2") (pintype "passive"))
    )
    (net (code "70") (name "Net-(Q20-out)") (class "Default")
      (node (ref "Q20") (pin "3") (pinfunction "out_3") (pintype "passive"))
      (node (ref "R130") (pin "2") (pinfunction "2_2") (pintype "passive"))
      (node (ref "U300") (pin "3") (pinfunction "EN_3") (pintype "passive"))
    )
    (net (code "71") (name "Net-(Q22-out)") (class "Default")
      (node (ref "Q22") (pin "3") (pinfunction "out_3") (pintype "passive"))
      (node (ref "R174") (pin "2") (pinfunction "2_2") (pintype "passive"))
    )
    (net (code "72") (name "Net-(Q26-Pad1)") (class "Default")
      (node (ref "Q26") (pin "1") (pintype "passive"))
      (node (ref "R102") (pin "1") (pinfunction "1_1") (pintype "passive"))
      (node (ref "R105") (pin "1") (pinfunction "1_1") (pintype "passive"))
    )
    (net (code "73") (name "Net-(Q26-Pad2)") (class "Default")
      (node (ref "Q26") (pin "2") (pintype "passive"))
      (node (ref "R22") (pin "1") (pinfunction "1_1") (pintype "passive"))
      (node (ref "R62") (pin "2") (pinfunction "2_2") (pintype "passive"))
    )
    (net (code "74") (name "Net-(Q27-out)") (class "Default")
      (node (ref "Q27") (pin "3") (pinfunction "out_3") (pintype "passive"))
      (node (ref "R105") (pin "2") (pinfunction "2_2") (pintype "passive"))
    )
    (net (code "75") (name "Net-(R196-Pad2)") (class "Default")
      (node (ref "R196") (pin "2") (pinfunction "2_2") (pintype "passive"))
      (node (ref "R197") (pin "1") (pinfunction "1_1") (pintype "passive"))
    )
    (net (code "76") (name "Net-(U3-VOUT)") (class "Default")
      (node (ref "C100") (pin "1") (pinfunction "1_1") (pintype "passive"))
      (node (ref "CP19") (pin "1") (pinfunction "1_1") (pintype "passive"))
      (node (ref "R178") (pin "1") (pinfunction "1_1") (pintype "passive"))
      (node (ref "U3") (pin "3") (pinfunction "VOUT_3") (pintype "passive"))
    )
    (net (code "77") (name "Net-(U14-D0)") (class "Default")
      (node (ref "RL30") (pin "1") (pinfunction "1_1") (pintype "passive"))
      (node (ref "U14") (pin "15") (pinfunction "D0_15") (pintype "passive"))
    )
    (net (code "78") (name "Net-(U14-D1)") (class "Default")
      (node (ref "RL23") (pin "1") (pinfunction "1_1") (pintype "passive"))
      (node (ref "U14") (pin "1") (pinfunction "D1_1") (pintype "passive"))
    )
    (net (code "79") (name "Net-(U14-D2)") (class "Default")
      (node (ref "RL24") (pin "1") (pinfunction "1_1") (pintype "passive"))
      (node (ref "U14") (pin "2") (pinfunction "D2_2") (pintype "passive"))
    )
    (net (code "80") (name "Net-(U14-D3)") (class "Default")
      (node (ref "RL25") (pin "1") (pinfunction "1_1") (pintype "passive"))
      (node (ref "U14") (pin "3") (pinfunction "D3_3") (pintype "passive"))
    )
    (net (code "81") (name "Net-(U14-D4)") (class "Default")
      (node (ref "RL26") (pin "1") (pinfunction "1_1") (pintype "passive"))
      (node (ref "U14") (pin "4") (pinfunction "D4_4") (pintype "passive"))
    )
    (net (code "82") (name "Net-(U14-D5)") (class "Default")
      (node (ref "RL27") (pin "1") (pinfunction "1_1") (pintype "passive"))
      (node (ref "U14") (pin "5") (pinfunction "D5_5") (pintype "passive"))
    )
    (net (code "83") (name "Net-(U14-D6)") (class "Default")
      (node (ref "RL28") (pin "1") (pinfunction "1_1") (pintype "passive"))
      (node (ref "U14") (pin "6") (pinfunction "D6_6") (pintype "passive"))
    )
    (net (code "84") (name "Net-(U14-D7)") (class "Default")
      (node (ref "RL29") (pin "1") (pinfunction "1_1") (pintype "passive"))
      (node (ref "U14") (pin "7") (pinfunction "D7_7") (pintype "passive"))
    )
    (net (code "85") (name "Net-(U22-D0)") (class "Default")
      (node (ref "RL38") (pin "1") (pinfunction "1_1") (pintype "passive"))
      (node (ref "U22") (pin "15") (pinfunction "D0_15") (pintype "passive"))
    )
    (net (code "86") (name "Net-(U22-D1)") (class "Default")
      (node (ref "RL37") (pin "1") (pinfunction "1_1") (pintype "passive"))
      (node (ref "U22") (pin "1") (pinfunction "D1_1") (pintype "passive"))
    )
    (net (code "87") (name "Net-(U22-D2)") (class "Default")
      (node (ref "RL36") (pin "1") (pinfunction "1_1") (pintype "passive"))
      (node (ref "U22") (pin "2") (pinfunction "D2_2") (pintype "passive"))
    )
    (net (code "88") (name "Net-(U22-D3)") (class "Default")
      (node (ref "RL35") (pin "1") (pinfunction "1_1") (pintype "passive"))
      (node (ref "U22") (pin "3") (pinfunction "D3_3") (pintype "passive"))
    )
    (net (code "89") (name "Net-(U22-D4)") (class "Default")
      (node (ref "RL34") (pin "1") (pinfunction "1_1") (pintype "passive"))
      (node (ref "U22") (pin "4") (pinfunction "D4_4") (pintype "passive"))
    )
    (net (code "90") (name "Net-(U22-D5)") (class "Default")
      (node (ref "RL33") (pin "1") (pinfunction "1_1") (pintype "passive"))
      (node (ref "U22") (pin "5") (pinfunction "D5_5") (pintype "passive"))
    )
    (net (code "91") (name "Net-(U22-D6)") (class "Default")
      (node (ref "RL32") (pin "1") (pinfunction "1_1") (pintype "passive"))
      (node (ref "U22") (pin "6") (pinfunction "D6_6") (pintype "passive"))
    )
    (net (code "92") (name "Net-(U22-D7)") (class "Default")
      (node (ref "RL31") (pin "1") (pinfunction "1_1") (pintype "passive"))
      (node (ref "U22") (pin "7") (pinfunction "D7_7") (pintype "passive"))
    )
    (net (code "93") (name "Net-(U300-BST)") (class "Default")
      (node (ref "C19") (pin "2") (pinfunction "2_2") (pintype "passive"))
      (node (ref "R162") (pin "1") (pinfunction "1_1") (pintype "passive"))
      (node (ref "U300") (pin "7") (pinfunction "BST_7") (pintype "passive"))
    )
    (net (code "94") (name "Net-(U300-FB)") (class "Default")
      (node (ref "R195") (pin "2") (pinfunction "2_2") (pintype "passive"))
      (node (ref "U300") (pin "4") (pinfunction "FB_4") (pintype "passive"))
    )
    (net (code "95") (name "Net-(U300-SS)") (class "Default")
      (node (ref "C49") (pin "2") (pinfunction "2_2") (pintype "passive"))
      (node (ref "U300") (pin "5") (pinfunction "SS_5") (pintype "passive"))
    )
    (net (code "96") (name "Net-(U300-VO)") (class "Default")
      (node (ref "R163") (pin "1") (pinfunction "1_1") (pintype "passive"))
      (node (ref "R179") (pin "2") (pinfunction "2_2") (pintype "passive"))
      (node (ref "U300") (pin "6") (pinfunction "VO_6") (pintype "passive"))
    )
    (net (code "97") (name "V") (class "Default")
      (node (ref "C107") (pin "2") (pinfunction "2_2") (pintype "passive"))
      (node (ref "C108") (pin "2") (pinfunction "2_2") (pintype "passive"))
      (node (ref "C14") (pin "2") (pinfunction "2_2") (pintype "passive"))
      (node (ref "C2") (pin "2") (pinfunction "2_2") (pintype "passive"))
      (node (ref "C300") (pin "2") (pinfunction "2_2") (pintype "passive"))
      (node (ref "C83") (pin "2") (pinfunction "2_2") (pintype "passive"))
      (node (ref "CP1") (pin "1") (pinfunction "1_1") (pintype "passive"))
      (node (ref "CP15") (pin "1") (pinfunction "1_1") (pintype "passive"))
      (node (ref "D2") (pin "1") (pinfunction "1_1") (pintype "passive"))
      (node (ref "D7") (pin "2") (pinfunction "K_2") (pintype "passive"))
      (node (ref "L1") (pin "1") (pinfunction "1_1") (pintype "passive"))
      (node (ref "L4") (pin "1") (pinfunction "1_1") (pintype "passive"))
      (node (ref "R176") (pin "1") (pinfunction "1_1") (pintype "passive"))
    )
    (net (code "98") (name "unconnected-(DZ15-Pad5)") (class "Default")
      (node (ref "DZ15") (pin "5") (pintype "passive"))
    )
    (net (code "99") (name "unconnected-(DZ15-Pad6)") (class "Default")
      (node (ref "DZ15") (pin "6") (pintype "passive"))
    )
    (net (code "100") (name "unconnected-(TP1-Pad1)") (class "Default")
      (node (ref "TP1") (pin "1") (pinfunction "1_1") (pintype "passive"))
    )
    (net (code "101") (name "unconnected-(TP2-Pad1)") (class "Default")
      (node (ref "TP2") (pin "1") (pinfunction "1_1") (pintype "passive"))
    )
    (net (code "102") (name "unconnected-(TP3-Pad1)") (class "Default")
      (node (ref "TP3") (pin "1") (pinfunction "1_1") (pintype "passive"))
    )
    (net (code "103") (name "unconnected-(TP4-Pad1)") (class "Default")
      (node (ref "TP4") (pin "1") (pinfunction "1_1") (pintype "passive"))
    )
    (net (code "104") (name "unconnected-(U14-D7`-Pad9)") (class "Default")
      (node (ref "U14") (pin "9") (pinfunction "D7`_9") (pintype "passive"))
    )
    (net (code "105") (name "unconnected-(U22-D7`-Pad9)") (class "Default")
      (node (ref "U22") (pin "9") (pinfunction "D7`_9") (pintype "passive"))
    )
  )
)
